# M044B.net
KiCad netlist of a schematic drawn in EAGLE
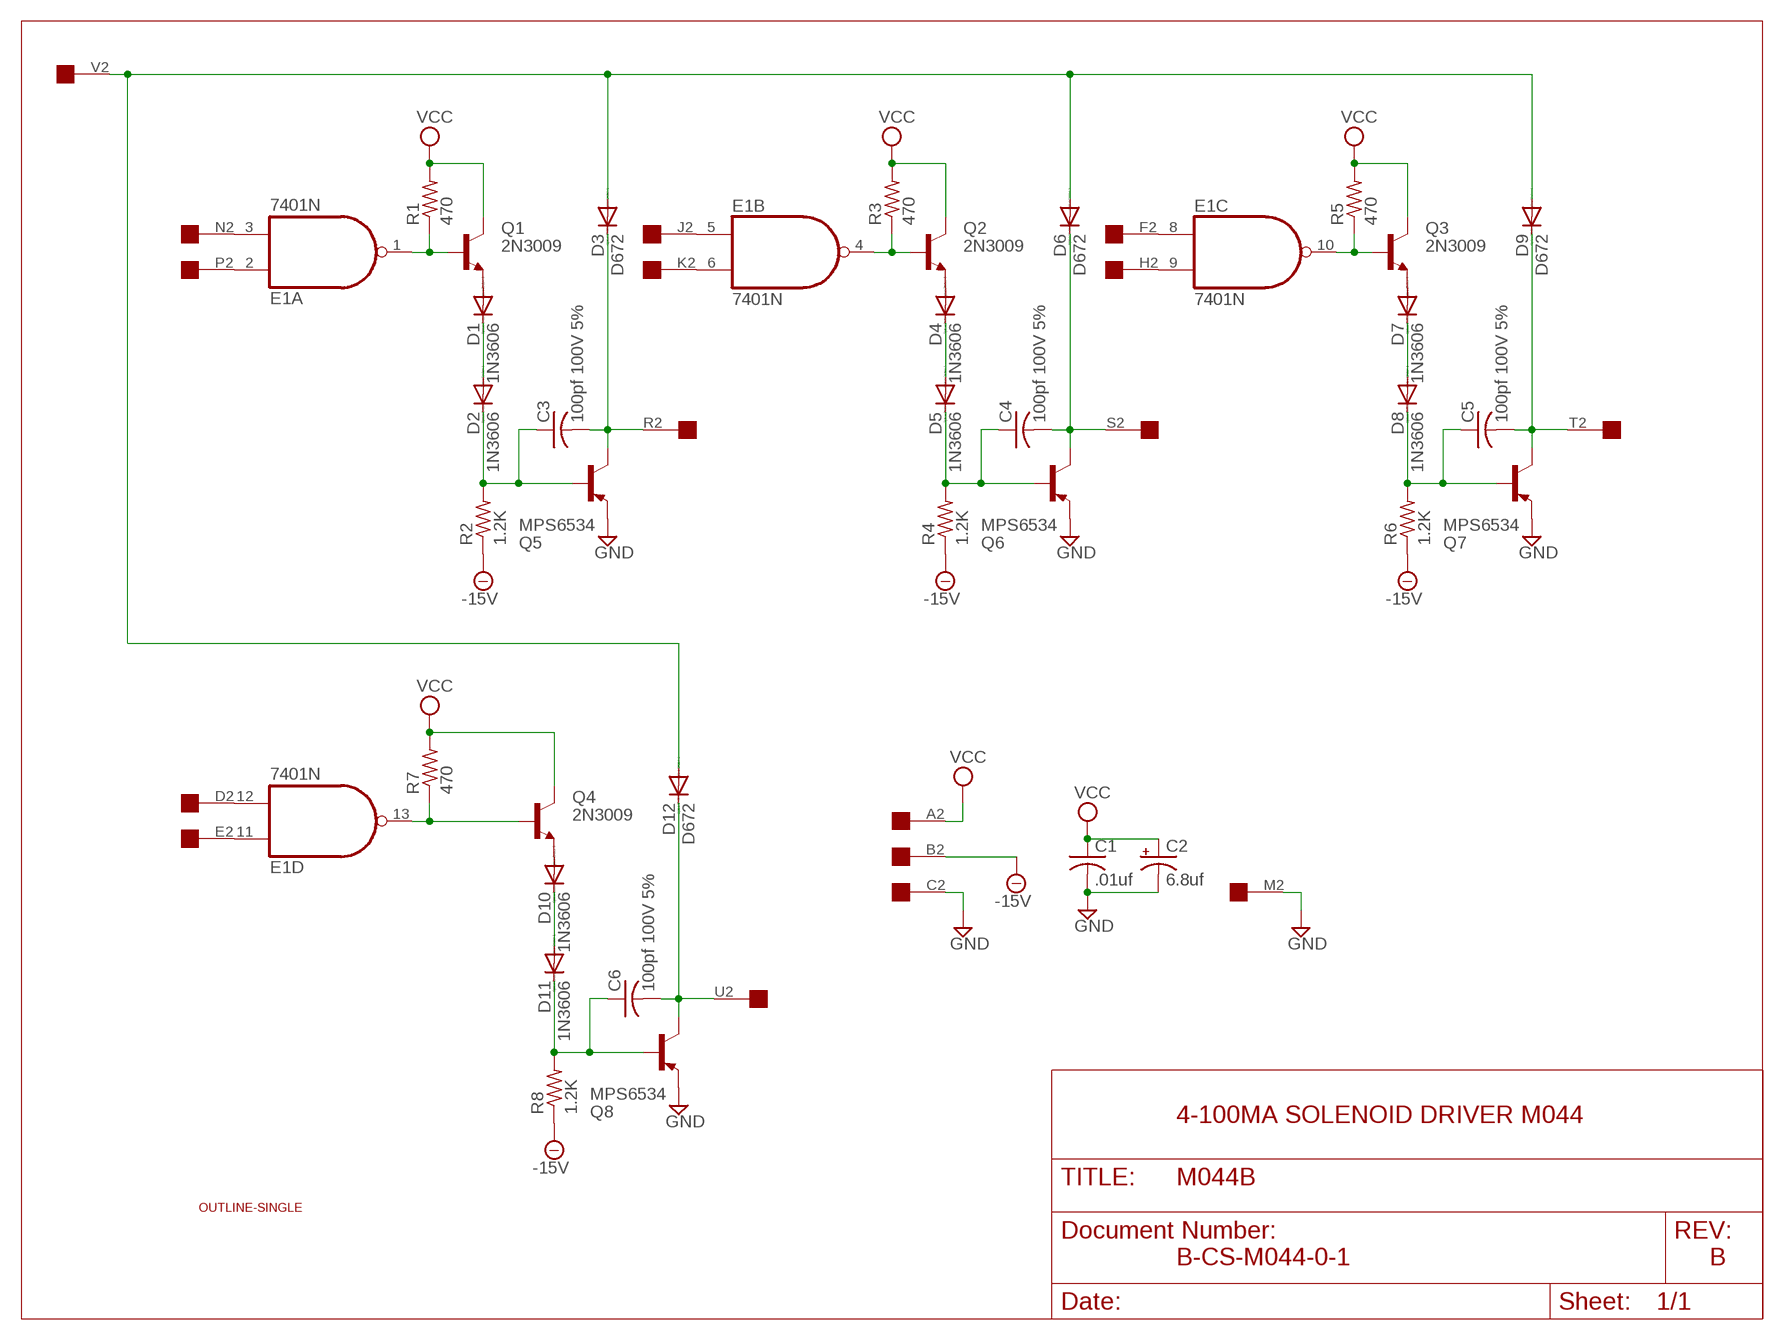
[diagram p0: schematic, sheet 1]

(export (version "E")
  (design (tool "Eeschema 10.0.6"))
  (components
    (comp (ref "C1")
      (value ".01uf")
      (footprint "eagle-import:C050-025X075")
      (libsource (lib "eagle-import") (part "C-US050-025X075"))
    )
    (comp (ref "C2")
      (value "6.8uf")
      (footprint "eagle-import:E15-5")
      (libsource (lib "eagle-import") (part "CPOL-USE15-5AXIAL"))
    )
    (comp (ref "C3")
      (value "100pf 100V 5%")
      (footprint "eagle-import:C050-025X075")
      (libsource (lib "eagle-import") (part "C-US050-025X075"))
    )
    (comp (ref "C4")
      (value "100pf 100V 5%")
      (footprint "eagle-import:C050-025X075")
      (libsource (lib "eagle-import") (part "C-US050-025X075"))
    )
    (comp (ref "C5")
      (value "100pf 100V 5%")
      (footprint "eagle-import:C050-025X075")
      (libsource (lib "eagle-import") (part "C-US050-025X075"))
    )
    (comp (ref "C6")
      (value "100pf 100V 5%")
      (footprint "eagle-import:C050-025X075")
      (libsource (lib "eagle-import") (part "C-US050-025X075"))
    )
    (comp (ref "D1")
      (value "1N3606")
      (footprint "eagle-import:DO35-10")
      (libsource (lib "eagle-import") (part "1N4148DO35-10"))
    )
    (comp (ref "D2")
      (value "1N3606")
      (footprint "eagle-import:DO35-10")
      (libsource (lib "eagle-import") (part "1N4148DO35-10"))
    )
    (comp (ref "D3")
      (value "D672")
      (footprint "eagle-import:DO35-10")
      (libsource (lib "eagle-import") (part "1N4148DO35-10"))
    )
    (comp (ref "D4")
      (value "1N3606")
      (footprint "eagle-import:DO35-10")
      (libsource (lib "eagle-import") (part "1N4148DO35-10"))
    )
    (comp (ref "D5")
      (value "1N3606")
      (footprint "eagle-import:DO35-10")
      (libsource (lib "eagle-import") (part "1N4148DO35-10"))
    )
    (comp (ref "D6")
      (value "D672")
      (footprint "eagle-import:DO35-10")
      (libsource (lib "eagle-import") (part "1N4148DO35-10"))
    )
    (comp (ref "D7")
      (value "1N3606")
      (footprint "eagle-import:DO35-10")
      (libsource (lib "eagle-import") (part "1N4148DO35-10"))
    )
    (comp (ref "D8")
      (value "1N3606")
      (footprint "eagle-import:DO35-10")
      (libsource (lib "eagle-import") (part "1N4148DO35-10"))
    )
    (comp (ref "D9")
      (value "D672")
      (footprint "eagle-import:DO35-10")
      (libsource (lib "eagle-import") (part "1N4148DO35-10"))
    )
    (comp (ref "D10")
      (value "1N3606")
      (footprint "eagle-import:DO35-10")
      (libsource (lib "eagle-import") (part "1N4148DO35-10"))
    )
    (comp (ref "D11")
      (value "1N3606")
      (footprint "eagle-import:DO35-10")
      (libsource (lib "eagle-import") (part "1N4148DO35-10"))
    )
    (comp (ref "D12")
      (value "D672")
      (footprint "eagle-import:DO35-10")
      (libsource (lib "eagle-import") (part "1N4148DO35-10"))
    )
    (comp (ref "E1")
      (value "7401N")
      (footprint "eagle-import:DIL14")
      (libsource (lib "eagle-import") (part "7401NLS"))
    )
    (comp (ref "Q1")
      (value "2N3009")
      (footprint "eagle-import:TO39")
      (libsource (lib "eagle-import") (part "2N3019"))
    )
    (comp (ref "Q2")
      (value "2N3009")
      (footprint "eagle-import:TO39")
      (libsource (lib "eagle-import") (part "2N3019"))
    )
    (comp (ref "Q3")
      (value "2N3009")
      (footprint "eagle-import:TO39")
      (libsource (lib "eagle-import") (part "2N3019"))
    )
    (comp (ref "Q4")
      (value "2N3009")
      (footprint "eagle-import:TO39")
      (libsource (lib "eagle-import") (part "2N3019"))
    )
    (comp (ref "Q5")
      (value "MPS6534")
      (footprint "eagle-import:TO39")
      (libsource (lib "eagle-import") (part "-PNP-TO39-EBC2N2904"))
    )
    (comp (ref "Q6")
      (value "MPS6534")
      (footprint "eagle-import:TO39")
      (libsource (lib "eagle-import") (part "-PNP-TO39-EBC2N2904"))
    )
    (comp (ref "Q7")
      (value "MPS6534")
      (footprint "eagle-import:TO39")
      (libsource (lib "eagle-import") (part "-PNP-TO39-EBC2N2904"))
    )
    (comp (ref "Q8")
      (value "MPS6534")
      (footprint "eagle-import:TO39")
      (libsource (lib "eagle-import") (part "-PNP-TO39-EBC2N2904"))
    )
    (comp (ref "R1")
      (value "470")
      (footprint "eagle-import:0207_10")
      (libsource (lib "eagle-import") (part "R-US_0207/10"))
    )
    (comp (ref "R2")
      (value "1.2K")
      (footprint "eagle-import:0207_10")
      (libsource (lib "eagle-import") (part "R-US_0207/10"))
    )
    (comp (ref "R3")
      (value "470")
      (footprint "eagle-import:0207_10")
      (libsource (lib "eagle-import") (part "R-US_0207/10"))
    )
    (comp (ref "R4")
      (value "1.2K")
      (footprint "eagle-import:0207_10")
      (libsource (lib "eagle-import") (part "R-US_0207/10"))
    )
    (comp (ref "R5")
      (value "470")
      (footprint "eagle-import:0207_10")
      (libsource (lib "eagle-import") (part "R-US_0207/10"))
    )
    (comp (ref "R6")
      (value "1.2K")
      (footprint "eagle-import:0207_10")
      (libsource (lib "eagle-import") (part "R-US_0207/10"))
    )
    (comp (ref "R7")
      (value "470")
      (footprint "eagle-import:0207_10")
      (libsource (lib "eagle-import") (part "R-US_0207/10"))
    )
    (comp (ref "R8")
      (value "1.2K")
      (footprint "eagle-import:0207_10")
      (libsource (lib "eagle-import") (part "R-US_0207/10"))
    )
    (comp (ref "U$1")
      (value "OUTLINE-SINGLE")
      (footprint "eagle-import:SINGLE")
      (libsource (lib "eagle-import") (part "OUTLINE-SINGLE"))
    )
    (comp (ref "U$2")
      (value "EDGE-1")
      (footprint "eagle-import:EDGE-CON1")
      (libsource (lib "eagle-import") (part "EDGE-1"))
    )
  )
  (nets
    (net (code "1") (name "-15V") (class "Default")
      (node (ref "R2") (pin "1") (pinfunction "1_1") (pintype "passive"))
      (node (ref "R4") (pin "1") (pinfunction "1_1") (pintype "passive"))
      (node (ref "R6") (pin "1") (pinfunction "1_1") (pintype "passive"))
      (node (ref "R8") (pin "1") (pinfunction "1_1") (pintype "passive"))
      (node (ref "U$2") (pin "B2") (pinfunction "1_B2") (pintype "bidirectional"))
    )
    (net (code "2") (name "GND") (class "Default")
      (node (ref "C1") (pin "2") (pinfunction "2_2") (pintype "passive"))
      (node (ref "C2") (pin "-") (pinfunction "-_-") (pintype "passive"))
      (node (ref "Q5") (pin "1") (pinfunction "E_1") (pintype "passive"))
      (node (ref "Q6") (pin "1") (pinfunction "E_1") (pintype "passive"))
      (node (ref "Q7") (pin "1") (pinfunction "E_1") (pintype "passive"))
      (node (ref "Q8") (pin "1") (pinfunction "E_1") (pintype "passive"))
      (node (ref "U$2") (pin "C2") (pinfunction "1_C2") (pintype "bidirectional"))
      (node (ref "U$2") (pin "M2") (pinfunction "1_M2") (pintype "bidirectional"))
    )
    (net (code "3") (name "Net-(D1-PadC)") (class "Default")
      (node (ref "D1") (pin "C") (pinfunction "C_C") (pintype "passive"))
      (node (ref "D2") (pin "A") (pinfunction "A_A") (pintype "passive"))
    )
    (net (code "4") (name "Net-(D4-PadC)") (class "Default")
      (node (ref "D4") (pin "C") (pinfunction "C_C") (pintype "passive"))
      (node (ref "D5") (pin "A") (pinfunction "A_A") (pintype "passive"))
    )
    (net (code "5") (name "Net-(D7-PadC)") (class "Default")
      (node (ref "D7") (pin "C") (pinfunction "C_C") (pintype "passive"))
      (node (ref "D8") (pin "A") (pinfunction "A_A") (pintype "passive"))
    )
    (net (code "6") (name "Net-(D10-PadC)") (class "Default")
      (node (ref "D10") (pin "C") (pinfunction "C_C") (pintype "passive"))
      (node (ref "D11") (pin "A") (pinfunction "A_A") (pintype "passive"))
    )
    (net (code "7") (name "Net-(E1A-I0)") (class "Default")
      (node (ref "E1") (pin "2") (pinfunction "I0_2") (pintype "input"))
      (node (ref "U$2") (pin "P2") (pinfunction "1_P2") (pintype "bidirectional"))
    )
    (net (code "8") (name "Net-(E1A-I1)") (class "Default")
      (node (ref "E1") (pin "3") (pinfunction "I1_3") (pintype "input"))
      (node (ref "U$2") (pin "N2") (pinfunction "1_N2") (pintype "bidirectional"))
    )
    (net (code "9") (name "Net-(E1A-O)") (class "Default")
      (node (ref "E1") (pin "1") (pinfunction "O_1") (pintype "open_collector"))
      (node (ref "Q1") (pin "2") (pinfunction "B_2") (pintype "passive"))
      (node (ref "R1") (pin "1") (pinfunction "1_1") (pintype "passive"))
    )
    (net (code "10") (name "Net-(E1B-I0)") (class "Default")
      (node (ref "E1") (pin "5") (pinfunction "I0_5") (pintype "input"))
      (node (ref "U$2") (pin "J2") (pinfunction "1_J2") (pintype "bidirectional"))
    )
    (net (code "11") (name "Net-(E1B-I1)") (class "Default")
      (node (ref "E1") (pin "6") (pinfunction "I1_6") (pintype "input"))
      (node (ref "U$2") (pin "K2") (pinfunction "1_K2") (pintype "bidirectional"))
    )
    (net (code "12") (name "Net-(E1B-O)") (class "Default")
      (node (ref "E1") (pin "4") (pinfunction "O_4") (pintype "open_collector"))
      (node (ref "Q2") (pin "2") (pinfunction "B_2") (pintype "passive"))
      (node (ref "R3") (pin "1") (pinfunction "1_1") (pintype "passive"))
    )
    (net (code "13") (name "Net-(E1C-I0)") (class "Default")
      (node (ref "E1") (pin "8") (pinfunction "I0_8") (pintype "input"))
      (node (ref "U$2") (pin "F2") (pinfunction "1_F2") (pintype "bidirectional"))
    )
    (net (code "14") (name "Net-(E1C-I1)") (class "Default")
      (node (ref "E1") (pin "9") (pinfunction "I1_9") (pintype "input"))
      (node (ref "U$2") (pin "H2") (pinfunction "1_H2") (pintype "bidirectional"))
    )
    (net (code "15") (name "Net-(E1C-O)") (class "Default")
      (node (ref "E1") (pin "10") (pinfunction "O_10") (pintype "open_collector"))
      (node (ref "Q3") (pin "2") (pinfunction "B_2") (pintype "passive"))
      (node (ref "R5") (pin "1") (pinfunction "1_1") (pintype "passive"))
    )
    (net (code "16") (name "Net-(E1D-I0)") (class "Default")
      (node (ref "E1") (pin "11") (pinfunction "I0_11") (pintype "input"))
      (node (ref "U$2") (pin "E2") (pinfunction "1_E2") (pintype "bidirectional"))
    )
    (net (code "17") (name "Net-(E1D-I1)") (class "Default")
      (node (ref "E1") (pin "12") (pinfunction "I1_12") (pintype "input"))
      (node (ref "U$2") (pin "D2") (pinfunction "1_D2") (pintype "bidirectional"))
    )
    (net (code "18") (name "Net-(E1D-O)") (class "Default")
      (node (ref "E1") (pin "13") (pinfunction "O_13") (pintype "open_collector"))
      (node (ref "Q4") (pin "2") (pinfunction "B_2") (pintype "passive"))
      (node (ref "R7") (pin "1") (pinfunction "1_1") (pintype "passive"))
    )
    (net (code "19") (name "Net-(Q1-E)") (class "Default")
      (node (ref "D1") (pin "A") (pinfunction "A_A") (pintype "passive"))
      (node (ref "Q1") (pin "1") (pinfunction "E_1") (pintype "passive"))
    )
    (net (code "20") (name "Net-(Q2-E)") (class "Default")
      (node (ref "D4") (pin "A") (pinfunction "A_A") (pintype "passive"))
      (node (ref "Q2") (pin "1") (pinfunction "E_1") (pintype "passive"))
    )
    (net (code "21") (name "Net-(Q3-E)") (class "Default")
      (node (ref "D7") (pin "A") (pinfunction "A_A") (pintype "passive"))
      (node (ref "Q3") (pin "1") (pinfunction "E_1") (pintype "passive"))
    )
    (net (code "22") (name "Net-(Q4-E)") (class "Default")
      (node (ref "D10") (pin "A") (pinfunction "A_A") (pintype "passive"))
      (node (ref "Q4") (pin "1") (pinfunction "E_1") (pintype "passive"))
    )
    (net (code "23") (name "Net-(Q5-B)") (class "Default")
      (node (ref "C3") (pin "1") (pinfunction "1_1") (pintype "passive"))
      (node (ref "D2") (pin "C") (pinfunction "C_C") (pintype "passive"))
      (node (ref "Q5") (pin "2") (pinfunction "B_2") (pintype "passive"))
      (node (ref "R2") (pin "2") (pinfunction "2_2") (pintype "passive"))
    )
    (net (code "24") (name "Net-(Q5-C)") (class "Default")
      (node (ref "C3") (pin "2") (pinfunction "2_2") (pintype "passive"))
      (node (ref "D3") (pin "C") (pinfunction "C_C") (pintype "passive"))
      (node (ref "Q5") (pin "3") (pinfunction "C_3") (pintype "passive"))
      (node (ref "U$2") (pin "R2") (pinfunction "1_R2") (pintype "bidirectional"))
    )
    (net (code "25") (name "Net-(Q6-B)") (class "Default")
      (node (ref "C4") (pin "1") (pinfunction "1_1") (pintype "passive"))
      (node (ref "D5") (pin "C") (pinfunction "C_C") (pintype "passive"))
      (node (ref "Q6") (pin "2") (pinfunction "B_2") (pintype "passive"))
      (node (ref "R4") (pin "2") (pinfunction "2_2") (pintype "passive"))
    )
    (net (code "26") (name "Net-(Q6-C)") (class "Default")
      (node (ref "C4") (pin "2") (pinfunction "2_2") (pintype "passive"))
      (node (ref "D6") (pin "C") (pinfunction "C_C") (pintype "passive"))
      (node (ref "Q6") (pin "3") (pinfunction "C_3") (pintype "passive"))
      (node (ref "U$2") (pin "S2") (pinfunction "1_S2") (pintype "bidirectional"))
    )
    (net (code "27") (name "Net-(Q7-B)") (class "Default")
      (node (ref "C5") (pin "1") (pinfunction "1_1") (pintype "passive"))
      (node (ref "D8") (pin "C") (pinfunction "C_C") (pintype "passive"))
      (node (ref "Q7") (pin "2") (pinfunction "B_2") (pintype "passive"))
      (node (ref "R6") (pin "2") (pinfunction "2_2") (pintype "passive"))
    )
    (net (code "28") (name "Net-(Q7-C)") (class "Default")
      (node (ref "C5") (pin "2") (pinfunction "2_2") (pintype "passive"))
      (node (ref "D9") (pin "C") (pinfunction "C_C") (pintype "passive"))
      (node (ref "Q7") (pin "3") (pinfunction "C_3") (pintype "passive"))
      (node (ref "U$2") (pin "T2") (pinfunction "1_T2") (pintype "bidirectional"))
    )
    (net (code "29") (name "Net-(Q8-B)") (class "Default")
      (node (ref "C6") (pin "1") (pinfunction "1_1") (pintype "passive"))
      (node (ref "D11") (pin "C") (pinfunction "C_C") (pintype "passive"))
      (node (ref "Q8") (pin "2") (pinfunction "B_2") (pintype "passive"))
      (node (ref "R8") (pin "2") (pinfunction "2_2") (pintype "passive"))
    )
    (net (code "30") (name "Net-(Q8-C)") (class "Default")
      (node (ref "C6") (pin "2") (pinfunction "2_2") (pintype "passive"))
      (node (ref "D12") (pin "C") (pinfunction "C_C") (pintype "passive"))
      (node (ref "Q8") (pin "3") (pinfunction "C_3") (pintype "passive"))
      (node (ref "U$2") (pin "U2") (pinfunction "1_U2") (pintype "bidirectional"))
    )
    (net (code "31") (name "Net-(U$2R-1)") (class "Default")
      (node (ref "D12") (pin "A") (pinfunction "A_A") (pintype "passive"))
      (node (ref "D3") (pin "A") (pinfunction "A_A") (pintype "passive"))
      (node (ref "D6") (pin "A") (pinfunction "A_A") (pintype "passive"))
      (node (ref "D9") (pin "A") (pinfunction "A_A") (pintype "passive"))
      (node (ref "U$2") (pin "V2") (pinfunction "1_V2") (pintype "bidirectional"))
    )
    (net (code "32") (name "VCC") (class "Default")
      (node (ref "C1") (pin "1") (pinfunction "1_1") (pintype "passive"))
      (node (ref "C2") (pin "+") (pinfunction "+_+") (pintype "passive"))
      (node (ref "Q1") (pin "3") (pinfunction "C_3") (pintype "passive"))
      (node (ref "Q2") (pin "3") (pinfunction "C_3") (pintype "passive"))
      (node (ref "Q3") (pin "3") (pinfunction "C_3") (pintype "passive"))
      (node (ref "Q4") (pin "3") (pinfunction "C_3") (pintype "passive"))
      (node (ref "R1") (pin "2") (pinfunction "2_2") (pintype "passive"))
      (node (ref "R3") (pin "2") (pinfunction "2_2") (pintype "passive"))
      (node (ref "R5") (pin "2") (pinfunction "2_2") (pintype "passive"))
      (node (ref "R7") (pin "2") (pinfunction "2_2") (pintype "passive"))
      (node (ref "U$2") (pin "A2") (pinfunction "1_A2") (pintype "bidirectional"))
    )
  )
)
